# uMultimeter_KEY_Sch.net
KiCad netlist of a schematic drawn in Altium Designer
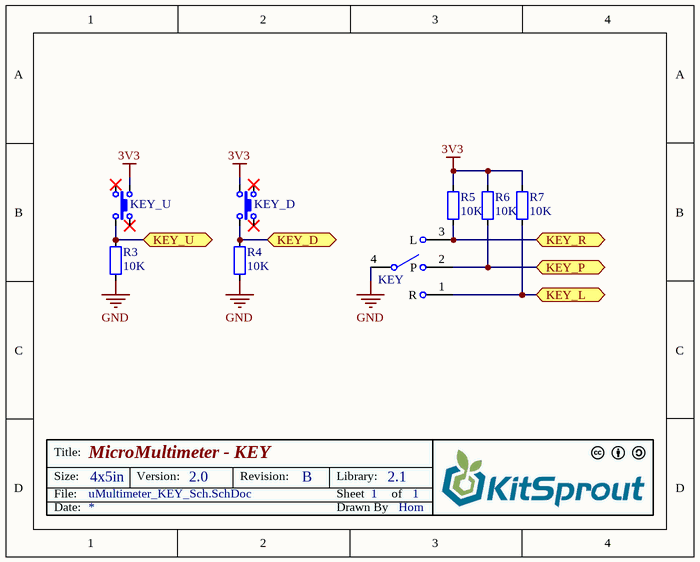
[diagram p0: uMultimeter_KEY_Sch.SchDoc]

(export (version "E")
  (design (tool "Eeschema 10.0.6"))
  (components
    (comp (ref "KEY")
      (value "ButtonPushLever_11*12_90")
      (footprint "PCB_Switch:ButtonPushLever_11*12_90")
      (description "Button")
      (libsource (lib "SCH_Switch") (part "ButtonPushLever_11*12_90"))
    )
    (comp (ref "KEY_D")
      (value "ButtonTACT")
      (footprint "PCB_Switch:ButtonTACT_3.5*3.55_90")
      (description "Button")
      (libsource (lib "SCH_Switch") (part "ButtonTACT"))
    )
    (comp (ref "KEY_U")
      (value "ButtonTACT")
      (footprint "PCB_Switch:ButtonTACT_3.5*3.55_90")
      (description "Button")
      (libsource (lib "SCH_Switch") (part "ButtonTACT"))
    )
    (comp (ref "R3")
      (value "10K")
      (footprint "PCB_PassiveRes:RES_0603")
      (description "Resistor")
      (fields (field (name "Comment") "Res_0603"))
      (libsource (lib "SCH_Passive") (part "Res_0603"))
    )
    (comp (ref "R4")
      (value "10K")
      (footprint "PCB_PassiveRes:RES_0603")
      (description "Resistor")
      (fields (field (name "Comment") "Res_0603"))
      (libsource (lib "SCH_Passive") (part "Res_0603"))
    )
    (comp (ref "R5")
      (value "10K")
      (footprint "PCB_PassiveRes:RES_0603")
      (description "Resistor")
      (fields (field (name "Comment") "Res_0603"))
      (libsource (lib "SCH_Passive") (part "Res_0603"))
    )
    (comp (ref "R6")
      (value "10K")
      (footprint "PCB_PassiveRes:RES_0603")
      (description "Resistor")
      (fields (field (name "Comment") "Res_0603"))
      (libsource (lib "SCH_Passive") (part "Res_0603"))
    )
    (comp (ref "R7")
      (value "10K")
      (footprint "PCB_PassiveRes:RES_0603")
      (description "Resistor")
      (fields (field (name "Comment") "Res_0603"))
      (libsource (lib "SCH_Passive") (part "Res_0603"))
    )
  )
  (nets
    (net (code "1") (name "/KEY_D") (class "Default")
      (node (ref "KEY_D") (pin "4") (pinfunction "4_4") (pintype "passive"))
      (node (ref "R4") (pin "2") (pinfunction "2_2") (pintype "passive"))
    )
    (net (code "2") (name "/KEY_L") (class "Default")
      (node (ref "KEY") (pin "1") (pinfunction "R_1") (pintype "passive"))
      (node (ref "R7") (pin "1") (pinfunction "1_1") (pintype "passive"))
    )
    (net (code "3") (name "/KEY_P") (class "Default")
      (node (ref "KEY") (pin "2") (pinfunction "P_2") (pintype "passive"))
      (node (ref "R6") (pin "1") (pinfunction "1_1") (pintype "passive"))
    )
    (net (code "4") (name "/KEY_R") (class "Default")
      (node (ref "KEY") (pin "3") (pinfunction "L_3") (pintype "passive"))
      (node (ref "R5") (pin "1") (pinfunction "1_1") (pintype "passive"))
    )
    (net (code "5") (name "/KEY_U") (class "Default")
      (node (ref "KEY_U") (pin "4") (pinfunction "4_4") (pintype "passive"))
      (node (ref "R3") (pin "2") (pinfunction "2_2") (pintype "passive"))
    )
    (net (code "6") (name "3V3") (class "Default")
      (node (ref "KEY_D") (pin "3") (pinfunction "3_3") (pintype "passive"))
      (node (ref "KEY_U") (pin "1") (pinfunction "1_1") (pintype "passive"))
      (node (ref "R5") (pin "2") (pinfunction "2_2") (pintype "passive"))
      (node (ref "R6") (pin "2") (pinfunction "2_2") (pintype "passive"))
      (node (ref "R7") (pin "2") (pinfunction "2_2") (pintype "passive"))
    )
    (net (code "7") (name "GND") (class "Default")
      (node (ref "KEY") (pin "4") (pinfunction "4_4") (pintype "passive"))
      (node (ref "R3") (pin "1") (pinfunction "1_1") (pintype "passive"))
      (node (ref "R4") (pin "1") (pinfunction "1_1") (pintype "passive"))
    )
    (net (code "8") (name "unconnected-(KEY_D-Pad1)") (class "Default")
      (node (ref "KEY_D") (pin "1") (pinfunction "1_1") (pintype "passive+no_connect"))
    )
    (net (code "9") (name "unconnected-(KEY_D-Pad2)") (class "Default")
      (node (ref "KEY_D") (pin "2") (pinfunction "2_2") (pintype "passive+no_connect"))
    )
    (net (code "10") (name "unconnected-(KEY_U-Pad2)") (class "Default")
      (node (ref "KEY_U") (pin "2") (pinfunction "2_2") (pintype "passive+no_connect"))
    )
    (net (code "11") (name "unconnected-(KEY_U-Pad3)") (class "Default")
      (node (ref "KEY_U") (pin "3") (pinfunction "3_3") (pintype "passive+no_connect"))
    )
  )
)
